# MyRollerShutter_nrf.net
KiCad netlist of a schematic drawn in EAGLE
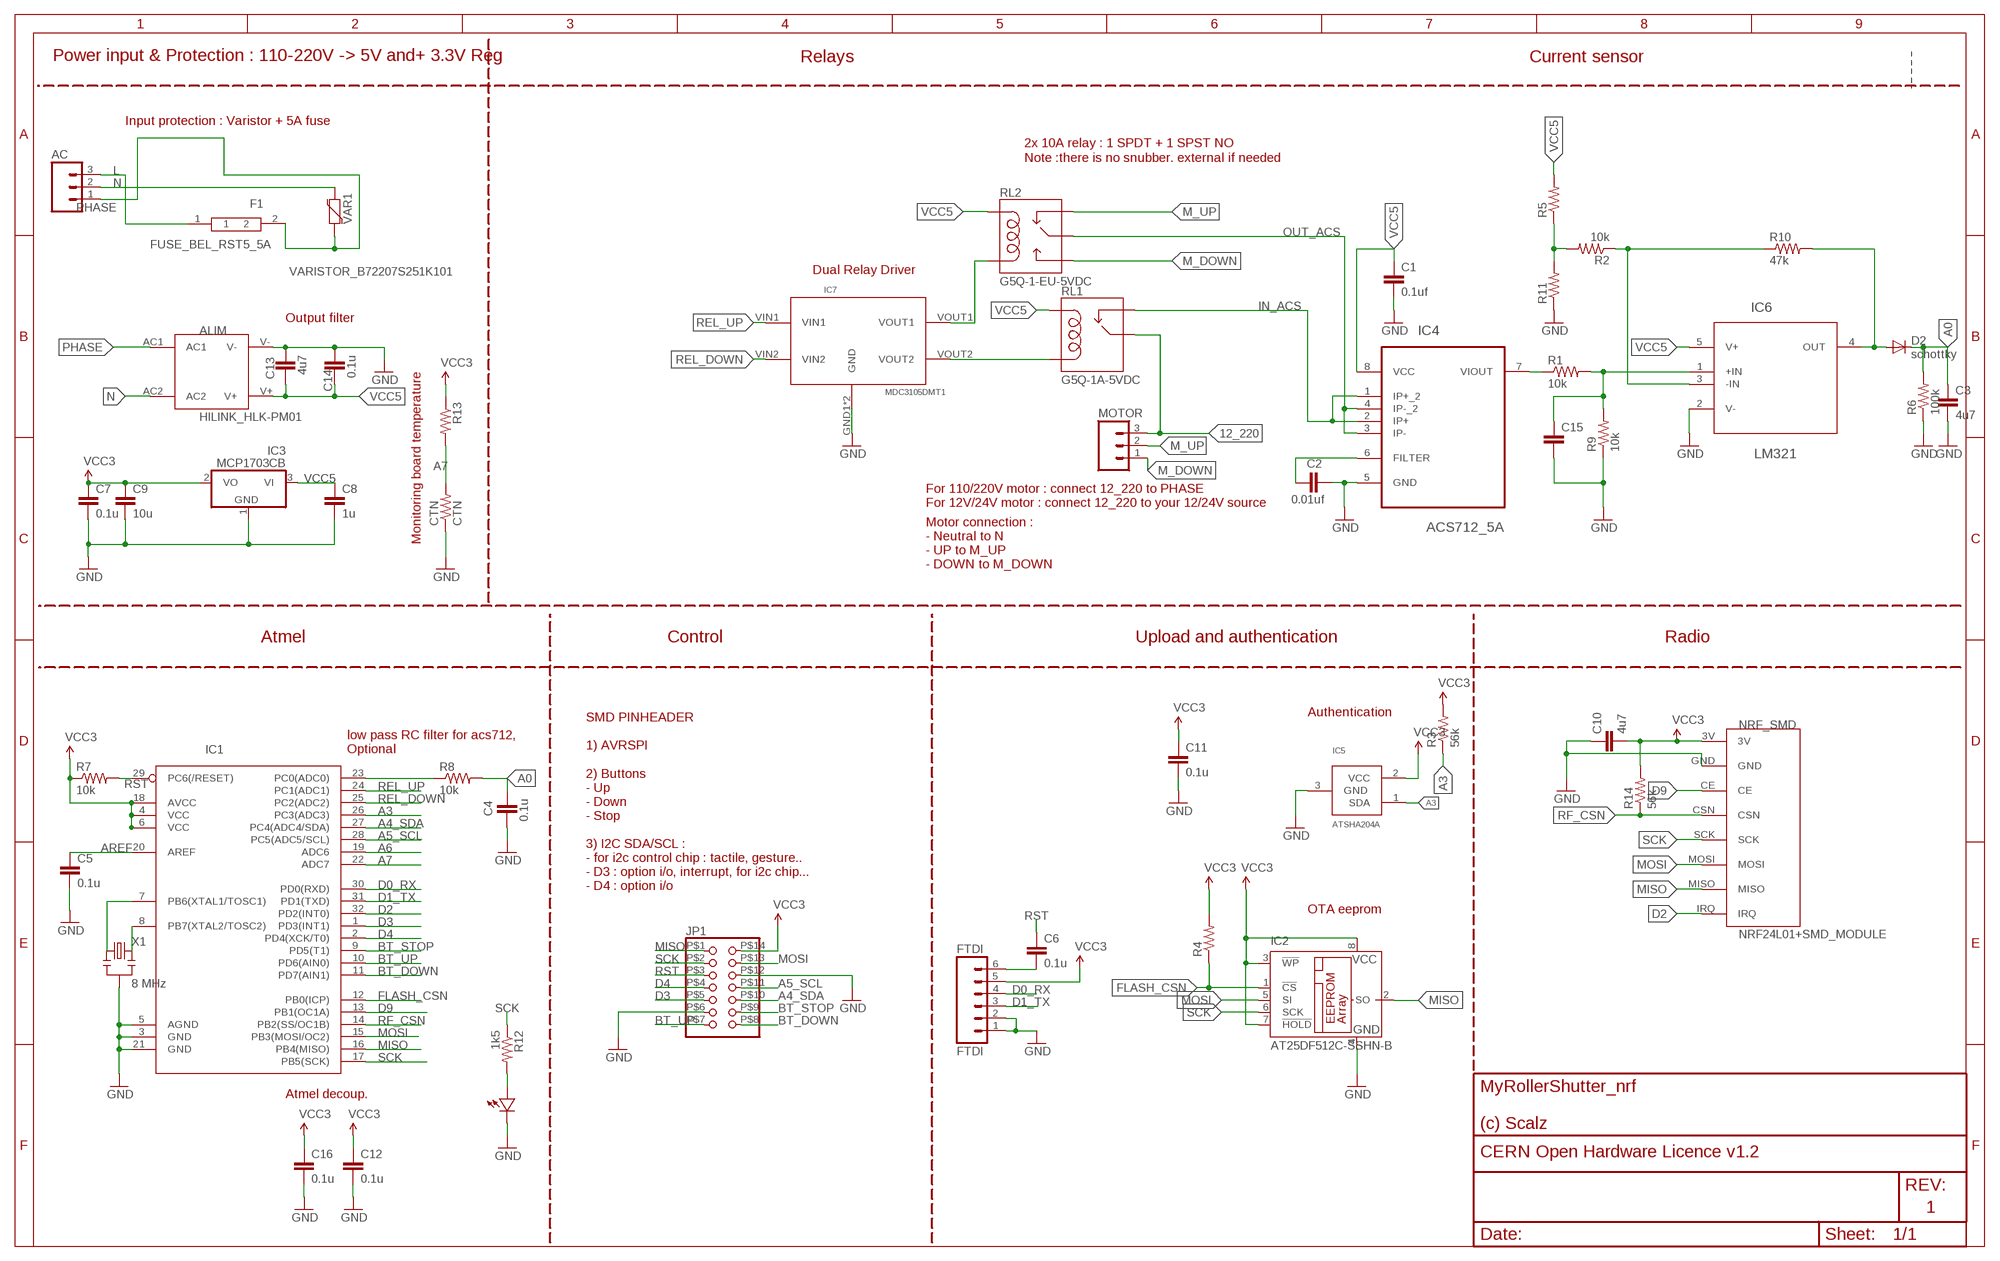
[diagram p0: schematic, sheet 1]

(export (version "E")
  (design (tool "Eeschema 10.0.6"))
  (components
    (comp (ref "AC")
      (value "M03-SCREW-5MM")
      (footprint "eagle-import:SCREWTERMINAL-5MM-3")
      (libsource (lib "eagle-import") (part "M03-SCREW-5MM"))
    )
    (comp (ref "ALIM")
      (value "HILINK_HLK-PM01")
      (footprint "eagle-import:HILINK_HLK-PM01")
      (libsource (lib "eagle-import") (part "HILINK_HLK-PM01"))
    )
    (comp (ref "C1")
      (value "0.1uf")
      (footprint "eagle-import:0805-CAP")
      (libsource (lib "eagle-import") (part "CAP0805-CAP"))
    )
    (comp (ref "C2")
      (value "0.01uf")
      (footprint "eagle-import:0805-CAP")
      (libsource (lib "eagle-import") (part "CAP0805-CAP"))
    )
    (comp (ref "C3")
      (value "4u7")
      (footprint "eagle-import:0805-CAP")
      (libsource (lib "eagle-import") (part "CAP0805-CAP"))
    )
    (comp (ref "C4")
      (value "0.1u")
      (footprint "eagle-import:0805-CAP")
      (libsource (lib "eagle-import") (part "CAP0805-CAP"))
    )
    (comp (ref "C5")
      (value "0.1u")
      (footprint "eagle-import:0805-CAP")
      (libsource (lib "eagle-import") (part "CAP0805-CAP"))
    )
    (comp (ref "C6")
      (value "0.1u")
      (footprint "eagle-import:0805-CAP")
      (libsource (lib "eagle-import") (part "CAP0805-CAP"))
    )
    (comp (ref "C7")
      (value "0.1u")
      (footprint "eagle-import:0805-CAP")
      (libsource (lib "eagle-import") (part "CAP0805-CAP"))
    )
    (comp (ref "C8")
      (value "1u")
      (footprint "eagle-import:0805-CAP")
      (libsource (lib "eagle-import") (part "CAP0805-CAP"))
    )
    (comp (ref "C9")
      (value "10u")
      (footprint "eagle-import:0805-CAP")
      (libsource (lib "eagle-import") (part "CAP0805-CAP"))
    )
    (comp (ref "C10")
      (value "4u7")
      (footprint "eagle-import:0805-CAP")
      (libsource (lib "eagle-import") (part "CAP0805-CAP"))
    )
    (comp (ref "C11")
      (value "0.1u")
      (footprint "eagle-import:0805-CAP")
      (libsource (lib "eagle-import") (part "CAP0805-CAP"))
    )
    (comp (ref "C12")
      (value "0.1u")
      (footprint "eagle-import:0805-CAP")
      (libsource (lib "eagle-import") (part "CAP0805-CAP"))
    )
    (comp (ref "C13")
      (value "4u7")
      (footprint "eagle-import:0805-CAP")
      (libsource (lib "eagle-import") (part "CAP0805-CAP"))
    )
    (comp (ref "C14")
      (value "0.1u")
      (footprint "eagle-import:0805-CAP")
      (libsource (lib "eagle-import") (part "CAP0805-CAP"))
    )
    (comp (ref "C15")
      (value "CAP0805-CAP")
      (footprint "eagle-import:0805-CAP")
      (libsource (lib "eagle-import") (part "CAP0805-CAP"))
    )
    (comp (ref "C16")
      (value "0.1u")
      (footprint "eagle-import:0805-CAP")
      (libsource (lib "eagle-import") (part "CAP0805-CAP"))
    )
    (comp (ref "CTN")
      (value "CTN")
      (footprint "eagle-import:0805-RES")
      (libsource (lib "eagle-import") (part "RESISTOR0805-RES"))
    )
    (comp (ref "D1")
      (value "LED0805")
      (footprint "eagle-import:0805-LED")
      (libsource (lib "eagle-import") (part "LED0805"))
    )
    (comp (ref "D2")
      (value "schottky")
      (footprint "eagle-import:SOD-323")
      (libsource (lib "eagle-import") (part "DIODESOD"))
    )
    (comp (ref "F1")
      (value "FUSE_BEL_RST5_5A")
      (footprint "eagle-import:FUSE_BEL_RST5_5A")
      (libsource (lib "eagle-import") (part "FUSE_BEL_RST5_5A"))
    )
    (comp (ref "FTDI")
      (value "FTDI")
      (footprint "eagle-import:1X06")
      (libsource (lib "eagle-import") (part "M06SIP"))
    )
    (comp (ref "IC1")
      (value "ATMega-328")
      (footprint "eagle-import:TQFP32-08")
      (libsource (lib "eagle-import") (part "ATMEGA168/328TQFP32"))
    )
    (comp (ref "IC2")
      (value "AT25DF512C-SSHN-B")
      (footprint "eagle-import:SO-08")
      (fields (field (name "MF") "MICROCHIP") (field (name "MPN") "25AA080/SN"))
      (libsource (lib "eagle-import") (part "25SNAA080"))
    )
    (comp (ref "IC3")
      (value "MCP1703CB")
      (footprint "eagle-import:SOT23")
      (libsource (lib "eagle-import") (part "MCP1703CB"))
    )
    (comp (ref "IC4")
      (value "ACS712_5A")
      (footprint "eagle-import:SOIC127P600X175-8N")
      (fields (field (name "MPN") "ACS712ELCTR-20A-T"))
      (libsource (lib "eagle-import") (part "ACS712ELCTR-20A-T"))
    )
    (comp (ref "IC5")
      (value "ATSHA204A")
      (footprint "eagle-import:SOT23")
      (libsource (lib "eagle-import") (part "ATSHA204A"))
    )
    (comp (ref "IC6")
      (value "LM321")
      (footprint "eagle-import:SOT95P285X120-5N")
      (fields (field (name "MPN") "LM321MF"))
      (libsource (lib "eagle-import") (part "LM321MF"))
    )
    (comp (ref "IC7")
      (value "MDC3105DMT1")
      (footprint "eagle-import:MDC3105DMT1")
      (libsource (lib "eagle-import") (part "MDC3105DMT1"))
    )
    (comp (ref "JP1")
      (value "PINHD-2X7")
      (footprint "eagle-import:2X07")
      (libsource (lib "eagle-import") (part "PINHD-2X7"))
    )
    (comp (ref "MOTOR")
      (value "M03-SCREW-5MM")
      (footprint "eagle-import:SCREWTERMINAL-5MM-3")
      (libsource (lib "eagle-import") (part "M03-SCREW-5MM"))
    )
    (comp (ref "NRF_SMD")
      (value "NRF24L01+SMD_MODULE")
      (footprint "eagle-import:NRF24L01+SMD_MODULE")
      (libsource (lib "eagle-import") (part "NRF24L01+SMD_MODULE"))
    )
    (comp (ref "R1")
      (value "10k")
      (footprint "eagle-import:0805-RES")
      (libsource (lib "eagle-import") (part "RESISTOR0805-RES"))
    )
    (comp (ref "R2")
      (value "10k")
      (footprint "eagle-import:0805-RES")
      (libsource (lib "eagle-import") (part "RESISTOR0805-RES"))
    )
    (comp (ref "R3")
      (value "56k")
      (footprint "eagle-import:0805-RES")
      (libsource (lib "eagle-import") (part "RESISTOR0805-RES"))
    )
    (comp (ref "R4")
      (value "RESISTOR0805-RES")
      (footprint "eagle-import:0805-RES")
      (libsource (lib "eagle-import") (part "RESISTOR0805-RES"))
    )
    (comp (ref "R5")
      (value "RESISTOR0805-RES")
      (footprint "eagle-import:0805-RES")
      (libsource (lib "eagle-import") (part "RESISTOR0805-RES"))
    )
    (comp (ref "R6")
      (value "100k")
      (footprint "eagle-import:0805-RES")
      (libsource (lib "eagle-import") (part "RESISTOR0805-RES"))
    )
    (comp (ref "R7")
      (value "10k")
      (footprint "eagle-import:0805-RES")
      (libsource (lib "eagle-import") (part "RESISTOR0805-RES"))
    )
    (comp (ref "R8")
      (value "10k")
      (footprint "eagle-import:0805-RES")
      (libsource (lib "eagle-import") (part "RESISTOR0805-RES"))
    )
    (comp (ref "R9")
      (value "10k")
      (footprint "eagle-import:0805-RES")
      (libsource (lib "eagle-import") (part "RESISTOR0805-RES"))
    )
    (comp (ref "R10")
      (value "47k")
      (footprint "eagle-import:0805-RES")
      (libsource (lib "eagle-import") (part "RESISTOR0805-RES"))
    )
    (comp (ref "R11")
      (value "RESISTOR0805-RES")
      (footprint "eagle-import:0805-RES")
      (libsource (lib "eagle-import") (part "RESISTOR0805-RES"))
    )
    (comp (ref "R12")
      (value "1k5")
      (footprint "eagle-import:0805-RES")
      (libsource (lib "eagle-import") (part "RESISTOR0805-RES"))
    )
    (comp (ref "R13")
      (value "RESISTOR0805-RES")
      (footprint "eagle-import:0805-RES")
      (libsource (lib "eagle-import") (part "RESISTOR0805-RES"))
    )
    (comp (ref "R14")
      (value "56k")
      (footprint "eagle-import:0805-RES")
      (libsource (lib "eagle-import") (part "RESISTOR0805-RES"))
    )
    (comp (ref "RL1")
      (value "G5Q-1A-5VDC")
      (footprint "eagle-import:G5Q_SINGLE")
      (libsource (lib "eagle-import") (part "G5Q_SINGLE"))
    )
    (comp (ref "RL2")
      (value "G5Q-1-EU-5VDC")
      (footprint "eagle-import:RELAY-G5Q")
      (libsource (lib "eagle-import") (part "RELAYPTH"))
    )
    (comp (ref "VAR1")
      (value "VARISTOR_B72207S251K101")
      (footprint "eagle-import:VARISTOR_B72207S251K101")
      (libsource (lib "eagle-import") (part "VARISTOR_B72207S251K101"))
    )
    (comp (ref "X1")
      (value "8 MHz")
      (footprint "eagle-import:RESONATOR-SMD")
      (libsource (lib "eagle-import") (part "RESONATORSMD"))
    )
  )
  (nets
    (net (code "1") (name "/A4_SDA") (class "Default")
      (node (ref "IC1") (pin "27") (pinfunction "PC4(ADC4/SDA)_27") (pintype "bidirectional"))
      (node (ref "JP1") (pin "P$10") (pinfunction "10_P$10") (pintype "passive"))
    )
    (net (code "2") (name "/A5_SCL") (class "Default")
      (node (ref "IC1") (pin "28") (pinfunction "PC5(ADC5/SCL)_28") (pintype "bidirectional"))
      (node (ref "JP1") (pin "P$11") (pinfunction "8_P$11") (pintype "passive"))
    )
    (net (code "3") (name "/A6") (class "Default")
      (node (ref "IC1") (pin "19") (pinfunction "ADC6_19") (pintype "bidirectional"))
    )
    (net (code "4") (name "/A7") (class "Default")
      (node (ref "CTN") (pin "2") (pinfunction "2_2") (pintype "passive"))
      (node (ref "IC1") (pin "22") (pinfunction "ADC7_22") (pintype "bidirectional"))
      (node (ref "R13") (pin "2") (pinfunction "2_2") (pintype "passive"))
    )
    (net (code "5") (name "/AREF") (class "Default")
      (node (ref "C5") (pin "1") (pinfunction "1_1") (pintype "passive"))
      (node (ref "IC1") (pin "20") (pinfunction "AREF_20") (pintype "bidirectional"))
    )
    (net (code "6") (name "/BT_DOWN") (class "Default")
      (node (ref "IC1") (pin "11") (pinfunction "PD7(AIN1)_11") (pintype "bidirectional"))
      (node (ref "JP1") (pin "P$8") (pinfunction "14_P$8") (pintype "passive"))
    )
    (net (code "7") (name "/BT_STOP") (class "Default")
      (node (ref "IC1") (pin "9") (pinfunction "PD5(T1)_9") (pintype "bidirectional"))
      (node (ref "JP1") (pin "P$9") (pinfunction "12_P$9") (pintype "passive"))
    )
    (net (code "8") (name "/BT_UP") (class "Default")
      (node (ref "IC1") (pin "10") (pinfunction "PD6(AIN0)_10") (pintype "bidirectional"))
      (node (ref "JP1") (pin "P$7") (pinfunction "13_P$7") (pintype "passive"))
    )
    (net (code "9") (name "/D0_RX") (class "Default")
      (node (ref "FTDI") (pin "4") (pinfunction "4_4") (pintype "passive"))
      (node (ref "IC1") (pin "30") (pinfunction "PD0(RXD)_30") (pintype "bidirectional"))
    )
    (net (code "10") (name "/D1_TX") (class "Default")
      (node (ref "FTDI") (pin "3") (pinfunction "3_3") (pintype "passive"))
      (node (ref "IC1") (pin "31") (pinfunction "PD1(TXD)_31") (pintype "bidirectional"))
    )
    (net (code "11") (name "/D3") (class "Default")
      (node (ref "IC1") (pin "1") (pinfunction "PD3(INT1)_1") (pintype "bidirectional"))
      (node (ref "JP1") (pin "P$5") (pinfunction "9_P$5") (pintype "passive"))
    )
    (net (code "12") (name "/D4") (class "Default")
      (node (ref "IC1") (pin "2") (pinfunction "PD4(XCK/T0)_2") (pintype "bidirectional"))
      (node (ref "JP1") (pin "P$4") (pinfunction "7_P$4") (pintype "passive"))
    )
    (net (code "13") (name "/IN_ACS") (class "Default")
      (node (ref "IC4") (pin "1") (pinfunction "IP+_2_1") (pintype "input"))
      (node (ref "IC4") (pin "2") (pinfunction "IP+_2") (pintype "input"))
      (node (ref "RL1") (pin "3") (pinfunction "NC_3") (pintype "bidirectional"))
    )
    (net (code "14") (name "/L") (class "Default")
      (node (ref "AC") (pin "3") (pinfunction "3_3") (pintype "passive"))
      (node (ref "F1") (pin "1") (pinfunction "1_1") (pintype "bidirectional"))
    )
    (net (code "15") (name "/OUT_ACS") (class "Default")
      (node (ref "IC4") (pin "3") (pinfunction "IP-_3") (pintype "input"))
      (node (ref "IC4") (pin "4") (pinfunction "IP-_2_4") (pintype "input"))
      (node (ref "RL2") (pin "2") (pinfunction "MAIN_2") (pintype "bidirectional"))
    )
    (net (code "16") (name "/RST") (class "Default")
      (node (ref "C6") (pin "1") (pinfunction "1_1") (pintype "passive"))
      (node (ref "IC1") (pin "29") (pinfunction "PC6(/RESET)_29") (pintype "bidirectional"))
      (node (ref "JP1") (pin "P$3") (pinfunction "5_P$3") (pintype "passive"))
      (node (ref "R7") (pin "2") (pinfunction "2_2") (pintype "passive"))
    )
    (net (code "17") (name "12_220") (class "Default")
      (node (ref "MOTOR") (pin "3") (pinfunction "3_3") (pintype "passive"))
      (node (ref "RL1") (pin "2") (pinfunction "MAIN_2") (pintype "bidirectional"))
    )
    (net (code "18") (name "A0") (class "Default")
      (node (ref "C3") (pin "1") (pinfunction "1_1") (pintype "passive"))
      (node (ref "C4") (pin "2") (pinfunction "2_2") (pintype "passive"))
      (node (ref "D2") (pin "1") (pinfunction "C_1") (pintype "passive"))
      (node (ref "R6") (pin "2") (pinfunction "2_2") (pintype "passive"))
      (node (ref "R8") (pin "2") (pinfunction "2_2") (pintype "passive"))
    )
    (net (code "19") (name "A3") (class "Default")
      (node (ref "IC1") (pin "26") (pinfunction "PC3(ADC3)_26") (pintype "bidirectional"))
      (node (ref "IC5") (pin "1") (pinfunction "SDA_1") (pintype "bidirectional"))
      (node (ref "R3") (pin "1") (pinfunction "1_1") (pintype "passive"))
    )
    (net (code "20") (name "D2") (class "Default")
      (node (ref "IC1") (pin "32") (pinfunction "PD2(INT0)_32") (pintype "bidirectional"))
      (node (ref "NRF_SMD") (pin "IRQ") (pinfunction "IRQ_IRQ") (pintype "bidirectional"))
    )
    (net (code "21") (name "D9") (class "Default")
      (node (ref "IC1") (pin "13") (pinfunction "PB1(OC1A)_13") (pintype "bidirectional"))
      (node (ref "NRF_SMD") (pin "CE") (pinfunction "CE_CE") (pintype "bidirectional"))
    )
    (net (code "22") (name "FLASH_CSN") (class "Default")
      (node (ref "IC1") (pin "12") (pinfunction "PB0(ICP)_12") (pintype "bidirectional"))
      (node (ref "IC2") (pin "1") (pinfunction "~{CS}_1") (pintype "input"))
      (node (ref "R4") (pin "1") (pinfunction "1_1") (pintype "passive"))
    )
    (net (code "23") (name "GND") (class "Default")
      (node (ref "ALIM") (pin "V-") (pinfunction "V-_V-") (pintype "bidirectional"))
      (node (ref "C1") (pin "2") (pinfunction "2_2") (pintype "passive"))
      (node (ref "C10") (pin "1") (pinfunction "1_1") (pintype "passive"))
      (node (ref "C11") (pin "2") (pinfunction "2_2") (pintype "passive"))
      (node (ref "C12") (pin "2") (pinfunction "2_2") (pintype "passive"))
      (node (ref "C13") (pin "2") (pinfunction "2_2") (pintype "passive"))
      (node (ref "C14") (pin "2") (pinfunction "2_2") (pintype "passive"))
      (node (ref "C15") (pin "2") (pinfunction "2_2") (pintype "passive"))
      (node (ref "C16") (pin "2") (pinfunction "2_2") (pintype "passive"))
      (node (ref "C2") (pin "2") (pinfunction "2_2") (pintype "passive"))
      (node (ref "C3") (pin "2") (pinfunction "2_2") (pintype "passive"))
      (node (ref "C4") (pin "1") (pinfunction "1_1") (pintype "passive"))
      (node (ref "C5") (pin "2") (pinfunction "2_2") (pintype "passive"))
      (node (ref "C7") (pin "2") (pinfunction "2_2") (pintype "passive"))
      (node (ref "C8") (pin "2") (pinfunction "2_2") (pintype "passive"))
      (node (ref "C9") (pin "2") (pinfunction "2_2") (pintype "passive"))
      (node (ref "CTN") (pin "1") (pinfunction "1_1") (pintype "passive"))
      (node (ref "D1") (pin "MINUS") (pinfunction "MINUS_MINUS") (pintype "passive"))
      (node (ref "FTDI") (pin "1") (pinfunction "1_1") (pintype "passive"))
      (node (ref "FTDI") (pin "2") (pinfunction "2_2") (pintype "passive"))
      (node (ref "IC1") (pin "21") (pinfunction "GND_21") (pintype "bidirectional"))
      (node (ref "IC1") (pin "3") (pinfunction "GND_3") (pintype "bidirectional"))
      (node (ref "IC1") (pin "5") (pinfunction "AGND_5") (pintype "bidirectional"))
      (node (ref "IC2") (pin "4") (pinfunction "GND_4") (pintype "power_in"))
      (node (ref "IC3") (pin "1") (pinfunction "GND_1") (pintype "passive"))
      (node (ref "IC4") (pin "5") (pinfunction "GND_5") (pintype "passive"))
      (node (ref "IC5") (pin "3") (pinfunction "GND_3") (pintype "bidirectional"))
      (node (ref "IC6") (pin "2") (pinfunction "V-_2") (pintype "power_in"))
      (node (ref "IC7") (pin "GND1") (pinfunction "GND_GND1") (pintype "bidirectional"))
      (node (ref "IC7") (pin "GND2") (pinfunction "GND_GND2") (pintype "bidirectional"))
      (node (ref "JP1") (pin "P$12") (pinfunction "6_P$12") (pintype "passive"))
      (node (ref "JP1") (pin "P$6") (pinfunction "11_P$6") (pintype "passive"))
      (node (ref "NRF_SMD") (pin "GND") (pinfunction "GND_GND") (pintype "bidirectional"))
      (node (ref "R11") (pin "1") (pinfunction "1_1") (pintype "passive"))
      (node (ref "R6") (pin "1") (pinfunction "1_1") (pintype "passive"))
      (node (ref "R9") (pin "1") (pinfunction "1_1") (pintype "passive"))
      (node (ref "X1") (pin "2") (pinfunction "2_2") (pintype "passive"))
    )
    (net (code "24") (name "MISO") (class "Default")
      (node (ref "IC1") (pin "16") (pinfunction "PB4(MISO)_16") (pintype "bidirectional"))
      (node (ref "IC2") (pin "2") (pinfunction "SO_2") (pintype "bidirectional"))
      (node (ref "JP1") (pin "P$1") (pinfunction "1_P$1") (pintype "passive"))
      (node (ref "NRF_SMD") (pin "MISO") (pinfunction "MISO_MISO") (pintype "bidirectional"))
    )
    (net (code "25") (name "MOSI") (class "Default")
      (node (ref "IC1") (pin "15") (pinfunction "PB3(MOSI/OC2)_15") (pintype "bidirectional"))
      (node (ref "IC2") (pin "5") (pinfunction "SI_5") (pintype "input"))
      (node (ref "JP1") (pin "P$13") (pinfunction "4_P$13") (pintype "passive"))
      (node (ref "NRF_SMD") (pin "MOSI") (pinfunction "MOSI_MOSI") (pintype "bidirectional"))
    )
    (net (code "26") (name "M_DOWN") (class "Default")
      (node (ref "MOTOR") (pin "1") (pinfunction "1_1") (pintype "passive"))
      (node (ref "RL2") (pin "3") (pinfunction "NO_3") (pintype "bidirectional"))
    )
    (net (code "27") (name "M_UP") (class "Default")
      (node (ref "MOTOR") (pin "2") (pinfunction "2_2") (pintype "passive"))
      (node (ref "RL2") (pin "4") (pinfunction "NC_4") (pintype "bidirectional"))
    )
    (net (code "28") (name "N") (class "Default")
      (node (ref "AC") (pin "2") (pinfunction "2_2") (pintype "passive"))
      (node (ref "ALIM") (pin "AC2") (pinfunction "AC2_AC2") (pintype "bidirectional"))
      (node (ref "VAR1") (pin "1") (pinfunction "1_1") (pintype "passive"))
    )
    (net (code "29") (name "Net-(C6-Pad2)") (class "Default")
      (node (ref "C6") (pin "2") (pinfunction "2_2") (pintype "passive"))
      (node (ref "FTDI") (pin "6") (pinfunction "6_6") (pintype "passive"))
    )
    (net (code "30") (name "Net-(D1-PadPLUS)") (class "Default")
      (node (ref "D1") (pin "PLUS") (pinfunction "PLUS_PLUS") (pintype "passive"))
      (node (ref "R12") (pin "2") (pinfunction "2_2") (pintype "passive"))
    )
    (net (code "31") (name "Net-(D2-A)") (class "Default")
      (node (ref "D2") (pin "2") (pinfunction "A_2") (pintype "passive"))
      (node (ref "IC6") (pin "4") (pinfunction "OUT_4") (pintype "output"))
      (node (ref "R10") (pin "2") (pinfunction "2_2") (pintype "passive"))
    )
    (net (code "32") (name "Net-(IC1-PB6(XTAL1{slash}TOSC1))") (class "Default")
      (node (ref "IC1") (pin "7") (pinfunction "PB6(XTAL1/TOSC1)_7") (pintype "bidirectional"))
      (node (ref "X1") (pin "1") (pinfunction "1_1") (pintype "passive"))
    )
    (net (code "33") (name "Net-(IC1-PB7(XTAL2{slash}TOSC2))") (class "Default")
      (node (ref "IC1") (pin "8") (pinfunction "PB7(XTAL2/TOSC2)_8") (pintype "bidirectional"))
      (node (ref "X1") (pin "3") (pinfunction "3_3") (pintype "passive"))
    )
    (net (code "34") (name "Net-(IC1-PC0(ADC0))") (class "Default")
      (node (ref "IC1") (pin "23") (pinfunction "PC0(ADC0)_23") (pintype "bidirectional"))
      (node (ref "R8") (pin "1") (pinfunction "1_1") (pintype "passive"))
    )
    (net (code "35") (name "Net-(IC4-FILTER)") (class "Default")
      (node (ref "C2") (pin "1") (pinfunction "1_1") (pintype "passive"))
      (node (ref "IC4") (pin "6") (pinfunction "FILTER_6") (pintype "input"))
    )
    (net (code "36") (name "Net-(IC4-VIOUT)") (class "Default")
      (node (ref "IC4") (pin "7") (pinfunction "VIOUT_7") (pintype "output"))
      (node (ref "R1") (pin "1") (pinfunction "1_1") (pintype "passive"))
    )
    (net (code "37") (name "Net-(IC6-+IN)") (class "Default")
      (node (ref "C15") (pin "1") (pinfunction "1_1") (pintype "passive"))
      (node (ref "IC6") (pin "1") (pinfunction "+IN_1") (pintype "input"))
      (node (ref "R1") (pin "2") (pinfunction "2_2") (pintype "passive"))
      (node (ref "R9") (pin "2") (pinfunction "2_2") (pintype "passive"))
    )
    (net (code "38") (name "Net-(IC6--IN)") (class "Default")
      (node (ref "IC6") (pin "3") (pinfunction "-IN_3") (pintype "input"))
      (node (ref "R10") (pin "1") (pinfunction "1_1") (pintype "passive"))
      (node (ref "R2") (pin "1") (pinfunction "1_1") (pintype "passive"))
    )
    (net (code "39") (name "Net-(R11-Pad2)") (class "Default")
      (node (ref "R11") (pin "2") (pinfunction "2_2") (pintype "passive"))
      (node (ref "R2") (pin "2") (pinfunction "2_2") (pintype "passive"))
      (node (ref "R5") (pin "1") (pinfunction "1_1") (pintype "passive"))
    )
    (net (code "40") (name "Net-(RL1-COIL2)") (class "Default")
      (node (ref "IC7") (pin "VOUT2") (pinfunction "VOUT2_VOUT2") (pintype "bidirectional"))
      (node (ref "RL1") (pin "5") (pinfunction "COIL2_5") (pintype "bidirectional"))
    )
    (net (code "41") (name "Net-(RL2-COIL2)") (class "Default")
      (node (ref "IC7") (pin "VOUT1") (pinfunction "VOUT1_VOUT1") (pintype "bidirectional"))
      (node (ref "RL2") (pin "1") (pinfunction "COIL2_1") (pintype "bidirectional"))
    )
    (net (code "42") (name "PHASE") (class "Default")
      (node (ref "AC") (pin "1") (pinfunction "1_1") (pintype "passive"))
      (node (ref "ALIM") (pin "AC1") (pinfunction "AC1_AC1") (pintype "bidirectional"))
      (node (ref "F1") (pin "2") (pinfunction "2_2") (pintype "bidirectional"))
      (node (ref "VAR1") (pin "2") (pinfunction "2_2") (pintype "passive"))
    )
    (net (code "43") (name "REL_DOWN") (class "Default")
      (node (ref "IC1") (pin "25") (pinfunction "PC2(ADC2)_25") (pintype "bidirectional"))
      (node (ref "IC7") (pin "VIN2") (pinfunction "VIN2_VIN2") (pintype "bidirectional"))
    )
    (net (code "44") (name "REL_UP") (class "Default")
      (node (ref "IC1") (pin "24") (pinfunction "PC1(ADC1)_24") (pintype "bidirectional"))
      (node (ref "IC7") (pin "VIN1") (pinfunction "VIN1_VIN1") (pintype "bidirectional"))
    )
    (net (code "45") (name "RF_CSN") (class "Default")
      (node (ref "IC1") (pin "14") (pinfunction "PB2(SS/OC1B)_14") (pintype "bidirectional"))
      (node (ref "NRF_SMD") (pin "CSN") (pinfunction "CSN_CSN") (pintype "bidirectional"))
      (node (ref "R14") (pin "1") (pinfunction "1_1") (pintype "passive"))
    )
    (net (code "46") (name "SCK") (class "Default")
      (node (ref "IC1") (pin "17") (pinfunction "PB5(SCK)_17") (pintype "bidirectional"))
      (node (ref "IC2") (pin "6") (pinfunction "SCK_6") (pintype "input"))
      (node (ref "JP1") (pin "P$2") (pinfunction "3_P$2") (pintype "passive"))
      (node (ref "NRF_SMD") (pin "SCK") (pinfunction "SCK_SCK") (pintype "bidirectional"))
      (node (ref "R12") (pin "1") (pinfunction "1_1") (pintype "passive"))
    )
    (net (code "47") (name "VCC3") (class "Default")
      (node (ref "C10") (pin "2") (pinfunction "2_2") (pintype "passive"))
      (node (ref "C11") (pin "1") (pinfunction "1_1") (pintype "passive"))
      (node (ref "C12") (pin "1") (pinfunction "1_1") (pintype "passive"))
      (node (ref "C16") (pin "1") (pinfunction "1_1") (pintype "passive"))
      (node (ref "C7") (pin "1") (pinfunction "1_1") (pintype "passive"))
      (node (ref "C9") (pin "1") (pinfunction "1_1") (pintype "passive"))
      (node (ref "FTDI") (pin "5") (pinfunction "5_5") (pintype "passive"))
      (node (ref "IC1") (pin "18") (pinfunction "AVCC_18") (pintype "bidirectional"))
      (node (ref "IC1") (pin "4") (pinfunction "VCC_4") (pintype "bidirectional"))
      (node (ref "IC1") (pin "6") (pinfunction "VCC_6") (pintype "bidirectional"))
      (node (ref "IC2") (pin "3") (pinfunction "~{WP}_3") (pintype "input"))
      (node (ref "IC2") (pin "7") (pinfunction "~{HOLD}_7") (pintype "input"))
      (node (ref "IC2") (pin "8") (pinfunction "VCC_8") (pintype "power_in"))
      (node (ref "IC3") (pin "2") (pinfunction "VO_2") (pintype "passive"))
      (node (ref "IC5") (pin "2") (pinfunction "VCC_2") (pintype "bidirectional"))
      (node (ref "JP1") (pin "P$14") (pinfunction "2_P$14") (pintype "passive"))
      (node (ref "NRF_SMD") (pin "3V") (pinfunction "3V_3V") (pintype "bidirectional"))
      (node (ref "R13") (pin "1") (pinfunction "1_1") (pintype "passive"))
      (node (ref "R14") (pin "2") (pinfunction "2_2") (pintype "passive"))
      (node (ref "R3") (pin "2") (pinfunction "2_2") (pintype "passive"))
      (node (ref "R4") (pin "2") (pinfunction "2_2") (pintype "passive"))
      (node (ref "R7") (pin "1") (pinfunction "1_1") (pintype "passive"))
    )
    (net (code "48") (name "VCC5") (class "Default")
      (node (ref "ALIM") (pin "V+") (pinfunction "V+_V+") (pintype "bidirectional"))
      (node (ref "C1") (pin "1") (pinfunction "1_1") (pintype "passive"))
      (node (ref "C13") (pin "1") (pinfunction "1_1") (pintype "passive"))
      (node (ref "C14") (pin "1") (pinfunction "1_1") (pintype "passive"))
      (node (ref "C8") (pin "1") (pinfunction "1_1") (pintype "passive"))
      (node (ref "IC3") (pin "3") (pinfunction "VI_3") (pintype "input"))
      (node (ref "IC4") (pin "8") (pinfunction "VCC_8") (pintype "power_in"))
      (node (ref "IC6") (pin "5") (pinfunction "V+_5") (pintype "power_in"))
      (node (ref "R5") (pin "2") (pinfunction "2_2") (pintype "passive"))
      (node (ref "RL1") (pin "1") (pinfunction "COIL1_1") (pintype "bidirectional"))
      (node (ref "RL2") (pin "5") (pinfunction "COIL1_5") (pintype "bidirectional"))
    )
  )
)
